# SWITCH.net
KiCad netlist of a schematic drawn in Altium Designer
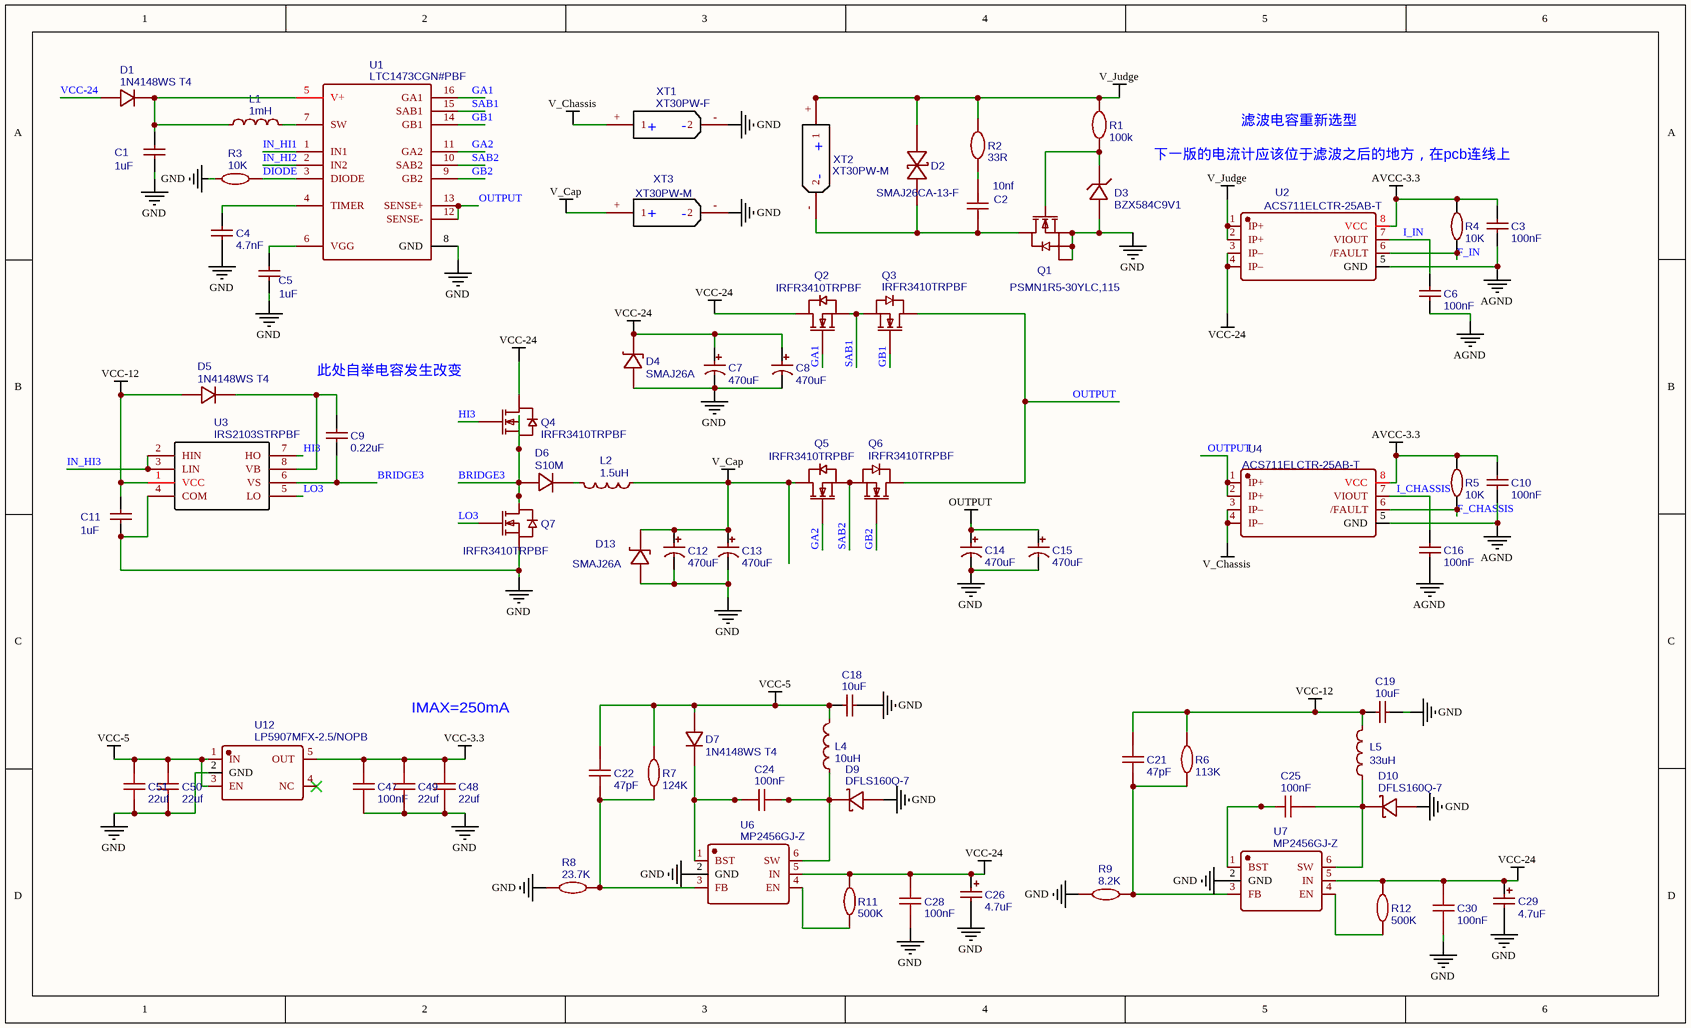
[diagram p0: SWITCH.SchDoc]

(export (version "E")
  (design (tool "Eeschema 10.0.6"))
  (components
    (comp (ref "C1")
      (value "1uF")
      (footprint "0603")
      (fields
        (field (name "BOM_MANUFACTURER PART") "CL10A105KB8NNNC")
        (field (name "BOM_SUPPLIER PART") "C15849")
      )
      (libsource (lib "altium-import") (part "root_3_1uF_"))
    )
    (comp (ref "C2")
      (value "10nf")
      (footprint "C0603")
      (libsource (lib "altium-import") (part "root_0_10nf_"))
    )
    (comp (ref "C3")
      (value "100nF")
      (footprint "L0603")
      (fields
        (field (name "BOM_MANUFACTURER PART") "CL05B104KO5NNNC")
        (field (name "BOM_SUPPLIER PART") "C1525")
      )
      (libsource (lib "") (part "root_1_100nF__1"))
    )
    (comp (ref "C4")
      (value "4.7nF")
      (footprint "C0603")
      (fields
        (field (name "BOM_MANUFACTURER PART") "0805B472K500NT")
        (field (name "BOM_SUPPLIER PART") "C1744")
      )
      (libsource (lib "altium-import") (part "root_1_4.7nF_"))
    )
    (comp (ref "C5")
      (value "1uF")
      (footprint "0603")
      (fields
        (field (name "BOM_MANUFACTURER PART") "CL10A105KB8NNNC")
        (field (name "BOM_SUPPLIER PART") "C15849")
      )
      (libsource (lib "altium-import") (part "root_3_1uF_"))
    )
    (comp (ref "C6")
      (value "100nF")
      (footprint "L0603")
      (fields
        (field (name "BOM_MANUFACTURER PART") "CL05B104KO5NNNC")
        (field (name "BOM_SUPPLIER PART") "C1525")
      )
      (libsource (lib "") (part "root_1_100nF__1"))
    )
    (comp (ref "C7")
      (value "470uF")
      (footprint "CAP-D12.5XF5.0")
      (fields (field (name "BOM_MANUFACTURER PART") "470μF 63V") (field (name "BOM_SUPPLIER PART") "C18823"))
      (libsource (lib "altium-import") (part "root_3_470uF_"))
    )
    (comp (ref "C8")
      (value "470uF")
      (footprint "CAP-D12.5XF5.0")
      (fields (field (name "BOM_MANUFACTURER PART") "470μF 63V") (field (name "BOM_SUPPLIER PART") "C18823"))
      (libsource (lib "altium-import") (part "root_3_470uF_"))
    )
    (comp (ref "C9")
      (value "0.22uF")
      (footprint "C0603")
      (libsource (lib "altium-import") (part "root_1_0.22uF_"))
    )
    (comp (ref "C10")
      (value "100nF")
      (footprint "L0603")
      (fields
        (field (name "BOM_MANUFACTURER PART") "CL05B104KO5NNNC")
        (field (name "BOM_SUPPLIER PART") "C1525")
      )
      (libsource (lib "") (part "root_1_100nF__1"))
    )
    (comp (ref "C11")
      (value "1uF")
      (footprint "0603")
      (fields
        (field (name "BOM_MANUFACTURER PART") "CL10A105KB8NNNC")
        (field (name "BOM_SUPPLIER PART") "C15849")
      )
      (libsource (lib "altium-import") (part "root_3_1uF_"))
    )
    (comp (ref "C12")
      (value "470uF")
      (footprint "CAP-D12.5XF5.0")
      (fields (field (name "BOM_MANUFACTURER PART") "470μF 63V") (field (name "BOM_SUPPLIER PART") "C18823"))
      (libsource (lib "altium-import") (part "root_3_470uF_"))
    )
    (comp (ref "C13")
      (value "470uF")
      (footprint "CAP-D12.5XF5.0")
      (fields (field (name "BOM_MANUFACTURER PART") "470μF 63V") (field (name "BOM_SUPPLIER PART") "C18823"))
      (libsource (lib "altium-import") (part "root_3_470uF_"))
    )
    (comp (ref "C14")
      (value "470uF")
      (footprint "CAP-D12.5XF5.0")
      (fields (field (name "BOM_MANUFACTURER PART") "470μF 63V") (field (name "BOM_SUPPLIER PART") "C18823"))
      (libsource (lib "altium-import") (part "root_3_470uF_"))
    )
    (comp (ref "C15")
      (value "470uF")
      (footprint "CAP-D12.5XF5.0")
      (fields (field (name "BOM_MANUFACTURER PART") "470μF 63V") (field (name "BOM_SUPPLIER PART") "C18823"))
      (libsource (lib "altium-import") (part "root_3_470uF_"))
    )
    (comp (ref "C16")
      (value "100nF")
      (footprint "L0603")
      (fields
        (field (name "BOM_MANUFACTURER PART") "CL05B104KO5NNNC")
        (field (name "BOM_SUPPLIER PART") "C1525")
      )
      (libsource (lib "") (part "root_1_100nF__1"))
    )
    (comp (ref "C18")
      (value "10uF")
      (footprint "0805")
      (fields
        (field (name "BOM_MANUFACTURER PART") "CL21A106KAYNNNE")
        (field (name "BOM_SUPPLIER PART") "C15850")
      )
      (libsource (lib "altium-import") (part "root_0_10uF_"))
    )
    (comp (ref "C19")
      (value "10uF")
      (footprint "0805")
      (fields
        (field (name "BOM_MANUFACTURER PART") "CL21A106KAYNNNE")
        (field (name "BOM_SUPPLIER PART") "C15850")
      )
      (libsource (lib "altium-import") (part "root_0_10uF_"))
    )
    (comp (ref "C21")
      (value "47pF")
      (footprint "0603")
      (fields
        (field (name "BOM_SUPPLIER PART") "C149616")
        (field (name "BOM_MANUFACTURER PART") "AC0603JRNPO9BN470")
        (field (name "CONTRIBUTOR") "LCSC")
      )
      (libsource (lib "altium-import") (part "root_2_47pF_"))
    )
    (comp (ref "C22")
      (value "47pF")
      (footprint "0603")
      (fields
        (field (name "BOM_SUPPLIER PART") "C149616")
        (field (name "BOM_MANUFACTURER PART") "AC0603JRNPO9BN470")
        (field (name "CONTRIBUTOR") "LCSC")
      )
      (libsource (lib "altium-import") (part "root_2_47pF_"))
    )
    (comp (ref "C24")
      (value "100nF")
      (footprint "0603")
      (fields
        (field (name "BOM_MANUFACTURER PART") "CC0603KRX7R9BB104")
        (field (name "BOM_SUPPLIER PART") "C14663")
      )
      (libsource (lib "altium-import") (part "root_0_100nF_"))
    )
    (comp (ref "C25")
      (value "100nF")
      (footprint "0603")
      (fields
        (field (name "BOM_MANUFACTURER PART") "CC0603KRX7R9BB104")
        (field (name "BOM_SUPPLIER PART") "C14663")
      )
      (libsource (lib "altium-import") (part "root_0_100nF_"))
    )
    (comp (ref "C26")
      (value "4.7uF")
      (footprint "CAP-CASE-A_3216")
      (fields
        (field (name "BOM_MANUFACTURER PART") "CA45-A-25V-4.7UF-K")
        (field (name "BOM_SUPPLIER PART") "C129569")
      )
      (libsource (lib "altium-import") (part "root_3_4.7uF_"))
    )
    (comp (ref "C28")
      (value "100nF")
      (footprint "0603")
      (fields
        (field (name "BOM_MANUFACTURER PART") "CC0603KRX7R9BB104")
        (field (name "BOM_SUPPLIER PART") "C14663")
      )
      (libsource (lib "altium-import") (part "root_1_100nF_"))
    )
    (comp (ref "C29")
      (value "4.7uF")
      (footprint "CAP-CASE-A_3216")
      (fields
        (field (name "BOM_MANUFACTURER PART") "CA45-A-25V-4.7UF-K")
        (field (name "BOM_SUPPLIER PART") "C129569")
      )
      (libsource (lib "altium-import") (part "root_3_4.7uF_"))
    )
    (comp (ref "C30")
      (value "100nF")
      (footprint "0603")
      (fields
        (field (name "BOM_MANUFACTURER PART") "CC0603KRX7R9BB104")
        (field (name "BOM_SUPPLIER PART") "C14663")
      )
      (libsource (lib "altium-import") (part "root_1_100nF_"))
    )
    (comp (ref "C47")
      (value "100nF")
      (footprint "C0603")
      (fields
        (field (name "BOM_MANUFACTURER PART") "GRM188R71H104KA93D")
        (field (name "BOM_SUPPLIER PART") "C77055")
      )
      (libsource (lib "altium-import") (part "root_1_100nF_"))
    )
    (comp (ref "C48")
      (value "22uf")
      (footprint "C0805")
      (fields (field (name "BOM_SUPPLIER PART") "C19704") (field (name "CONTRIBUTOR") "LCSC"))
      (libsource (lib "altium-import") (part "root_0_22uf_"))
    )
    (comp (ref "C49")
      (value "22uf")
      (footprint "C0805")
      (fields (field (name "BOM_SUPPLIER PART") "C19704") (field (name "CONTRIBUTOR") "LCSC"))
      (libsource (lib "altium-import") (part "root_0_22uf_"))
    )
    (comp (ref "C50")
      (value "22uf")
      (footprint "C0805")
      (fields (field (name "BOM_SUPPLIER PART") "C19704") (field (name "CONTRIBUTOR") "LCSC"))
      (libsource (lib "altium-import") (part "root_0_22uf_"))
    )
    (comp (ref "C51")
      (value "22uf")
      (footprint "C0805")
      (fields (field (name "BOM_SUPPLIER PART") "C19704") (field (name "CONTRIBUTOR") "LCSC"))
      (libsource (lib "altium-import") (part "root_0_22uf_"))
    )
    (comp (ref "D1")
      (value "1N4148WS T4")
      (footprint "SOD-323_L1.8-W1.3-LS2.5-FD")
      (fields (field (name "BOM_SUPPLIER PART") "C2128"))
      (libsource (lib "altium-import") (part "root_0_1N4148WS T4_"))
    )
    (comp (ref "D2")
      (value "SMAJ26CA-13-F")
      (footprint "SMA_L4.4-W2.6-LS5.0-BI")
      (fields (field (name "BOM_SUPPLIER PART") "C134976") (field (name "CONTRIBUTOR") "LCSC"))
      (libsource (lib "altium-import") (part "root_1_SMAJ26CA-13-F_"))
    )
    (comp (ref "D3")
      (value "BZX584C9V1")
      (footprint "SOD-523F_L1.7-W0.9-LS1.7-RD")
      (libsource (lib "altium-import") (part "root_3_BZX584C9V1_"))
    )
    (comp (ref "D4")
      (value "SMAJ26A")
      (footprint "SMA(DO-214AC)")
      (fields (field (name "BOM_SUPPLIER PART") "C49370"))
      (libsource (lib "altium-import") (part "root_1_SMAJ26A_"))
    )
    (comp (ref "D5")
      (value "1N4148WS T4")
      (footprint "SOD-323_L1.8-W1.3-LS2.5-FD")
      (fields (field (name "BOM_SUPPLIER PART") "C2128"))
      (libsource (lib "altium-import") (part "root_0_1N4148WS T4_"))
    )
    (comp (ref "D6")
      (value "S10M")
      (footprint "SMC(DO-214AB)")
      (fields (field (name "BOM_SUPPLIER PART") "C64933"))
      (libsource (lib "altium-import") (part "root_2_S10M_"))
    )
    (comp (ref "D7")
      (value "1N4148WS T4")
      (footprint "SOD-323_L1.8-W1.3-LS2.5-FD")
      (fields (field (name "BOM_SUPPLIER PART") "C2128"))
      (libsource (lib "altium-import") (part "root_3_1N4148WS T4_"))
    )
    (comp (ref "D9")
      (value "DFLS160Q-7")
      (footprint "POWERDI-123")
      (fields (field (name "BOM_SUPPLIER PART") "C211394") (field (name "CONTRIBUTOR") "LCSC"))
      (libsource (lib "altium-import") (part "root_2_DFLS160Q-7_"))
    )
    (comp (ref "D10")
      (value "DFLS160Q-7")
      (footprint "POWERDI-123")
      (fields (field (name "BOM_SUPPLIER PART") "C211394") (field (name "CONTRIBUTOR") "LCSC"))
      (libsource (lib "altium-import") (part "root_2_DFLS160Q-7_"))
    )
    (comp (ref "D13")
      (value "SMAJ26A")
      (footprint "SMA(DO-214AC)")
      (fields (field (name "BOM_SUPPLIER PART") "C49370"))
      (libsource (lib "altium-import") (part "root_1_SMAJ26A_"))
    )
    (comp (ref "L1")
      (value "1mH")
      (footprint "IND-SMD_L4.0-W4.0")
      (fields
        (field (name "BOM_SUPPLIER PART") "C354594")
        (field (name "BOM_MANUFACTURER PART") "CKCS4030-1mH/M")
        (field (name "CONTRIBUTOR") "LCSC")
      )
      (libsource (lib "altium-import") (part "root_0_1mH_"))
    )
    (comp (ref "L2")
      (value "1.5uH")
      (footprint "SMD-L-13.5X12.8X5.0")
      (fields
        (field (name "BOM_MANUFACTURER PART") "MWSA1205-1R5MT")
        (field (name "BOM_SUPPLIER PART") "C149569")
        (field (name "CONTRIBUTOR") "LCSC")
      )
      (libsource (lib "altium-import") (part "root_2_1.5uH_"))
    )
    (comp (ref "L4")
      (value "10uH")
      (footprint "R0603")
      (fields
        (field (name "BOM_MANUFACTURER PART") "SDFL2012S100KTF")
        (field (name "BOM_SUPPLIER PART") "C1046")
      )
      (libsource (lib "altium-import") (part "root_1_10uH_"))
    )
    (comp (ref "L5")
      (value "33uH")
      (footprint "1008")
      (fields
        (field (name "BOM_MANUFACTURER PART") "NLV25T-330J-PF")
        (field (name "BOM_SUPPLIER PART") "C136257")
      )
      (libsource (lib "altium-import") (part "root_1_33uH_"))
    )
    (comp (ref "Q1")
      (value "PSMN1R5-30YLC,115")
      (footprint "SOT-669_L4.9-W4.0-P1.27-LS6.0-BR")
      (fields (field (name "BOM_SUPPLIER PART") "C427523") (field (name "CONTRIBUTOR") "LCSC"))
      (libsource (lib "altium-import") (part "root_3_PSMN1R5-30YLC,115_"))
    )
    (comp (ref "Q2")
      (value "IRFR3410TRPBF")
      (footprint "TO-252-2")
      (fields (field (name "BOM_SUPPLIER PART") "C3016"))
      (libsource (lib "") (part "root_1_IRFR3410TRPBF__1"))
    )
    (comp (ref "Q3")
      (value "IRFR3410TRPBF")
      (footprint "TO-252-2")
      (fields (field (name "BOM_SUPPLIER PART") "C3016"))
      (libsource (lib "altium-import") (part "root_1_IRFR3410TRPBF_"))
    )
    (comp (ref "Q4")
      (value "IRFR3410TRPBF")
      (footprint "TO-252-2")
      (fields (field (name "BOM_SUPPLIER PART") "C3016"))
      (libsource (lib "altium-import") (part "root_0_IRFR3410TRPBF_"))
    )
    (comp (ref "Q5")
      (value "IRFR3410TRPBF")
      (footprint "TO-252-2")
      (fields (field (name "BOM_SUPPLIER PART") "C3016"))
      (libsource (lib "") (part "root_1_IRFR3410TRPBF__1"))
    )
    (comp (ref "Q6")
      (value "IRFR3410TRPBF")
      (footprint "TO-252-2")
      (fields (field (name "BOM_SUPPLIER PART") "C3016"))
      (libsource (lib "altium-import") (part "root_1_IRFR3410TRPBF_"))
    )
    (comp (ref "Q7")
      (value "IRFR3410TRPBF")
      (footprint "TO-252-2")
      (fields (field (name "BOM_SUPPLIER PART") "C3016"))
      (libsource (lib "altium-import") (part "root_0_IRFR3410TRPBF_"))
    )
    (comp (ref "R1")
      (value "100k")
      (footprint "R0603")
      (libsource (lib "altium-import") (part "root_1_100k_"))
    )
    (comp (ref "R2") (value "33R") (footprint "R0603") (libsource (lib "altium-import") (part "root_1_33R_")))
    (comp (ref "R3")
      (value "10K")
      (footprint "R0603")
      (fields
        (field (name "BOM_SUPPLIER PART") "C191557")
        (field (name "BOM_MANUFACTURER PART") "ERJ-6RBD1002V")
        (field (name "CONTRIBUTOR") "LCSC")
      )
      (libsource (lib "altium-import") (part "root_0_10K_"))
    )
    (comp (ref "R4")
      (value "10K")
      (footprint "R0603")
      (fields
        (field (name "BOM_MANUFACTURER PART") "0402WGF1002TCE")
        (field (name "BOM_SUPPLIER PART") "C25744")
      )
      (libsource (lib "altium-import") (part "root_1_10K_"))
    )
    (comp (ref "R5")
      (value "10K")
      (footprint "R0603")
      (fields
        (field (name "BOM_MANUFACTURER PART") "0402WGF1002TCE")
        (field (name "BOM_SUPPLIER PART") "C25744")
      )
      (libsource (lib "altium-import") (part "root_1_10K_"))
    )
    (comp (ref "R6")
      (value "113K")
      (footprint "R0603")
      (fields
        (field (name "BOM_SUPPLIER PART") "C228262")
        (field (name "BOM_MANUFACTURER PART") "AC0805FR-07113KL")
        (field (name "CONTRIBUTOR") "LCSC")
      )
      (libsource (lib "altium-import") (part "root_1_113K_"))
    )
    (comp (ref "R7")
      (value "124K")
      (footprint "R0603")
      (fields
        (field (name "BOM_SUPPLIER PART") "C228280")
        (field (name "BOM_MANUFACTURER PART") "AC0805FR-07124KL")
        (field (name "CONTRIBUTOR") "LCSC")
      )
      (libsource (lib "altium-import") (part "root_1_124K_"))
    )
    (comp (ref "R8")
      (value "23.7K")
      (footprint "0805")
      (fields
        (field (name "BOM_SUPPLIER PART") "C322370")
        (field (name "BOM_MANUFACTURER PART") "RS-05K2372FT")
        (field (name "CONTRIBUTOR") "LCSC")
      )
      (libsource (lib "altium-import") (part "root_0_23.7K_"))
    )
    (comp (ref "R9")
      (value "8.2K")
      (footprint "R0603")
      (fields
        (field (name "BOM_MANUFACTURER PART") "WR08X822JTL")
        (field (name "BOM_SUPPLIER PART") "C171042")
        (field (name "CONTRIBUTOR") "LCSC")
      )
      (libsource (lib "altium-import") (part "root_0_8.2K_"))
    )
    (comp (ref "R11")
      (value "500K")
      (footprint "0805")
      (fields
        (field (name "BOM_SUPPLIER PART") "C316218")
        (field (name "BOM_MANUFACTURER PART") "AR05BTCW5003")
        (field (name "CONTRIBUTOR") "LCSC")
      )
      (libsource (lib "altium-import") (part "root_1_500K_"))
    )
    (comp (ref "R12")
      (value "500K")
      (footprint "0805")
      (fields
        (field (name "BOM_SUPPLIER PART") "C316218")
        (field (name "BOM_MANUFACTURER PART") "AR05BTCW5003")
        (field (name "CONTRIBUTOR") "LCSC")
      )
      (libsource (lib "altium-import") (part "root_3_500K_"))
    )
    (comp (ref "U1")
      (value "LTC1473CGN#PBF")
      (footprint "TSSOP16")
      (libsource (lib "altium-import") (part "root_0_LTC1473CGN#PBF_"))
    )
    (comp (ref "U2")
      (value "ACS711ELCTR-25AB-T")
      (footprint "SOIC-8_150MIL")
      (fields (field (name "BOM_SUPPLIER PART") "C114268") (field (name "CONTRIBUTOR") "LCSC"))
      (libsource (lib "altium-import") (part "root_0_ACS711ELCTR-25AB-T_"))
    )
    (comp (ref "U3")
      (value "IRS2103STRPBF")
      (footprint "SOIC-8_150MIL")
      (fields (field (name "BOM_SUPPLIER PART") "C2958"))
      (libsource (lib "altium-import") (part "root_0_IRS2103STRPBF_"))
    )
    (comp (ref "U4")
      (value "ACS711ELCTR-25AB-T")
      (footprint "SOIC-8_150MIL")
      (fields (field (name "BOM_SUPPLIER PART") "C114268") (field (name "CONTRIBUTOR") "LCSC"))
      (libsource (lib "altium-import") (part "root_0_ACS711ELCTR-25AB-T_"))
    )
    (comp (ref "U6")
      (value "MP2456GJ-Z")
      (footprint "TSOT-23-6")
      (fields (field (name "BOM_SUPPLIER PART") "C88045"))
      (libsource (lib "altium-import") (part "root_0_MP2456GJ-Z_"))
    )
    (comp (ref "U7")
      (value "MP2456GJ-Z")
      (footprint "TSOT-23-6")
      (fields (field (name "BOM_SUPPLIER PART") "C88045"))
      (libsource (lib "altium-import") (part "root_0_MP2456GJ-Z_"))
    )
    (comp (ref "U12")
      (value "LP5907MFX-2.5/NOPB")
      (footprint "SOT-23-5_L3.0-W1.7-P0.95-LS2.8-BL")
      (fields (field (name "BOM_SUPPLIER PART") "C165132") (field (name "CONTRIBUTOR") "LCSC"))
      (libsource (lib "altium-import") (part "root_0_LP5907MFX-2.5/NOPB_"))
    )
    (comp (ref "XT1")
      (value "XT30PW-F")
      (footprint "XT30_H_F")
      (fields (field (name "BOM_MANUFACTURER PART") "XT60") (field (name "CONTRIBUTOR") "4bucks"))
      (libsource (lib "altium-import") (part "root_0_XT30PW-F_"))
    )
    (comp (ref "XT2")
      (value "XT30PW-M")
      (footprint "XT30PW")
      (fields (field (name "BOM_MANUFACTURER PART") "XT60") (field (name "CONTRIBUTOR") "4bucks"))
      (libsource (lib "altium-import") (part "root_3_XT30PW-M_"))
    )
    (comp (ref "XT3")
      (value "XT30PW-M")
      (footprint "XT30PW")
      (fields (field (name "BOM_MANUFACTURER PART") "XT60") (field (name "CONTRIBUTOR") "4bucks"))
      (libsource (lib "altium-import") (part "root_0_XT30PW-M_"))
    )
  )
  (nets
    (net (code "1") (name "/BRIDGE3") (class "Default")
      (node (ref "C9") (pin "1") (pinfunction "1_1") (pintype "passive"))
      (node (ref "D6") (pin "1") (pinfunction "A_1") (pintype "passive"))
      (node (ref "Q4") (pin "3") (pinfunction "S_3") (pintype "passive"))
      (node (ref "Q7") (pin "4") (pinfunction "D_4") (pintype "passive"))
      (node (ref "U3") (pin "6") (pinfunction "VS_6") (pintype "passive"))
    )
    (net (code "2") (name "/DIODE") (class "Default")
      (node (ref "R3") (pin "2") (pinfunction "2_2") (pintype "passive"))
      (node (ref "U1") (pin "3") (pinfunction "DIODE_3") (pintype "passive"))
    )
    (net (code "3") (name "/F_CHASSIS") (class "Default")
      (node (ref "R5") (pin "1") (pinfunction "1_1") (pintype "passive"))
      (node (ref "U4") (pin "6") (pinfunction "/FAULT_6") (pintype "passive"))
    )
    (net (code "4") (name "/F_IN") (class "Default")
      (node (ref "R4") (pin "1") (pinfunction "1_1") (pintype "passive"))
      (node (ref "U2") (pin "6") (pinfunction "/FAULT_6") (pintype "passive"))
    )
    (net (code "5") (name "/GA1") (class "Default")
      (node (ref "Q2") (pin "1") (pinfunction "G_1") (pintype "passive"))
      (node (ref "U1") (pin "16") (pinfunction "GA1_16") (pintype "passive"))
    )
    (net (code "6") (name "/GA2") (class "Default")
      (node (ref "Q5") (pin "1") (pinfunction "G_1") (pintype "passive"))
      (node (ref "U1") (pin "11") (pinfunction "GA2_11") (pintype "passive"))
    )
    (net (code "7") (name "/GB1") (class "Default")
      (node (ref "Q3") (pin "1") (pinfunction "G_1") (pintype "passive"))
      (node (ref "U1") (pin "14") (pinfunction "GB1_14") (pintype "passive"))
    )
    (net (code "8") (name "/GB2") (class "Default")
      (node (ref "Q6") (pin "1") (pinfunction "G_1") (pintype "passive"))
      (node (ref "U1") (pin "9") (pinfunction "GB2_9") (pintype "passive"))
    )
    (net (code "9") (name "/HI3") (class "Default")
      (node (ref "Q4") (pin "1") (pinfunction "G_1") (pintype "passive"))
      (node (ref "U3") (pin "7") (pinfunction "HO_7") (pintype "passive"))
    )
    (net (code "10") (name "/IN_HI1") (class "Default")
      (node (ref "U1") (pin "1") (pinfunction "IN1_1") (pintype "passive"))
    )
    (net (code "11") (name "/IN_HI2") (class "Default")
      (node (ref "U1") (pin "2") (pinfunction "IN2_2") (pintype "passive"))
    )
    (net (code "12") (name "/IN_HI3") (class "Default")
      (node (ref "U3") (pin "2") (pinfunction "HIN_2") (pintype "passive"))
      (node (ref "U3") (pin "3") (pinfunction "LIN_3") (pintype "passive"))
    )
    (net (code "13") (name "/I_CHASSIS") (class "Default")
      (node (ref "C16") (pin "2") (pinfunction "2_2") (pintype "passive"))
      (node (ref "U4") (pin "7") (pinfunction "VIOUT_7") (pintype "passive"))
    )
    (net (code "14") (name "/I_IN") (class "Default")
      (node (ref "C6") (pin "2") (pinfunction "2_2") (pintype "passive"))
      (node (ref "U2") (pin "7") (pinfunction "VIOUT_7") (pintype "passive"))
    )
    (net (code "15") (name "/LO3") (class "Default")
      (node (ref "Q7") (pin "1") (pinfunction "G_1") (pintype "passive"))
      (node (ref "U3") (pin "5") (pinfunction "LO_5") (pintype "passive"))
    )
    (net (code "16") (name "/SAB1") (class "Default")
      (node (ref "Q2") (pin "3") (pinfunction "S_3") (pintype "passive"))
      (node (ref "Q3") (pin "3") (pinfunction "S_3") (pintype "passive"))
      (node (ref "U1") (pin "15") (pinfunction "SAB1_15") (pintype "passive"))
    )
    (net (code "17") (name "/SAB2") (class "Default")
      (node (ref "Q5") (pin "3") (pinfunction "S_3") (pintype "passive"))
      (node (ref "Q6") (pin "3") (pinfunction "S_3") (pintype "passive"))
      (node (ref "U1") (pin "10") (pinfunction "SAB2_10") (pintype "passive"))
    )
    (net (code "18") (name "AGND") (class "Default")
      (node (ref "C10") (pin "1") (pinfunction "1_1") (pintype "passive"))
      (node (ref "C16") (pin "1") (pinfunction "1_1") (pintype "passive"))
      (node (ref "C3") (pin "1") (pinfunction "1_1") (pintype "passive"))
      (node (ref "C6") (pin "1") (pinfunction "1_1") (pintype "passive"))
      (node (ref "U2") (pin "5") (pinfunction "GND_5") (pintype "passive"))
      (node (ref "U4") (pin "5") (pinfunction "GND_5") (pintype "passive"))
    )
    (net (code "19") (name "AVCC-3.3") (class "Default")
      (node (ref "C10") (pin "2") (pinfunction "2_2") (pintype "passive"))
      (node (ref "C3") (pin "2") (pinfunction "2_2") (pintype "passive"))
      (node (ref "R4") (pin "2") (pinfunction "2_2") (pintype "passive"))
      (node (ref "R5") (pin "2") (pinfunction "2_2") (pintype "passive"))
      (node (ref "U2") (pin "8") (pinfunction "VCC_8") (pintype "passive"))
      (node (ref "U4") (pin "8") (pinfunction "VCC_8") (pintype "passive"))
    )
    (net (code "20") (name "GND") (class "Default")
      (node (ref "C1") (pin "2") (pinfunction "2_2") (pintype "passive"))
      (node (ref "C11") (pin "2") (pinfunction "2_2") (pintype "passive"))
      (node (ref "C12") (pin "2") (pinfunction "2_2") (pintype "passive"))
      (node (ref "C13") (pin "2") (pinfunction "2_2") (pintype "passive"))
      (node (ref "C14") (pin "2") (pinfunction "2_2") (pintype "passive"))
      (node (ref "C15") (pin "2") (pinfunction "2_2") (pintype "passive"))
      (node (ref "C18") (pin "2") (pinfunction "2_2") (pintype "passive"))
      (node (ref "C19") (pin "2") (pinfunction "2_2") (pintype "passive"))
      (node (ref "C26") (pin "2") (pinfunction "2_2") (pintype "passive"))
      (node (ref "C28") (pin "1") (pinfunction "1_1") (pintype "passive"))
      (node (ref "C29") (pin "2") (pinfunction "2_2") (pintype "passive"))
      (node (ref "C30") (pin "1") (pinfunction "1_1") (pintype "passive"))
      (node (ref "C4") (pin "1") (pinfunction "1_1") (pintype "passive"))
      (node (ref "C47") (pin "1") (pinfunction "1_1") (pintype "passive"))
      (node (ref "C48") (pin "1") (pinfunction "1_1") (pintype "passive"))
      (node (ref "C49") (pin "1") (pinfunction "1_1") (pintype "passive"))
      (node (ref "C5") (pin "2") (pinfunction "2_2") (pintype "passive"))
      (node (ref "C50") (pin "1") (pinfunction "1_1") (pintype "passive"))
      (node (ref "C51") (pin "1") (pinfunction "1_1") (pintype "passive"))
      (node (ref "C7") (pin "2") (pinfunction "2_2") (pintype "passive"))
      (node (ref "C8") (pin "2") (pinfunction "2_2") (pintype "passive"))
      (node (ref "D10") (pin "2") (pinfunction "2_2") (pintype "passive"))
      (node (ref "D13") (pin "1") (pinfunction "A_1") (pintype "passive"))
      (node (ref "D3") (pin "2") (pinfunction "A_2") (pintype "passive"))
      (node (ref "D4") (pin "1") (pinfunction "A_1") (pintype "passive"))
      (node (ref "D9") (pin "2") (pinfunction "2_2") (pintype "passive"))
      (node (ref "Q1") (pin "1") (pinfunction "S_1") (pintype "passive"))
      (node (ref "Q1") (pin "2") (pinfunction "S_2") (pintype "passive"))
      (node (ref "Q1") (pin "3") (pinfunction "S_3") (pintype "passive"))
      (node (ref "Q7") (pin "3") (pinfunction "S_3") (pintype "passive"))
      (node (ref "R3") (pin "1") (pinfunction "1_1") (pintype "passive"))
      (node (ref "R8") (pin "1") (pinfunction "1_1") (pintype "passive"))
      (node (ref "R9") (pin "1") (pinfunction "1_1") (pintype "passive"))
      (node (ref "U1") (pin "8") (pinfunction "GND_8") (pintype "passive"))
      (node (ref "U12") (pin "2") (pinfunction "GND_2") (pintype "passive"))
      (node (ref "U3") (pin "4") (pinfunction "COM_4") (pintype "passive"))
      (node (ref "U6") (pin "2") (pinfunction "GND_2") (pintype "passive"))
      (node (ref "U7") (pin "2") (pinfunction "GND_2") (pintype "passive"))
      (node (ref "XT1") (pin "-") (pinfunction "2_-") (pintype "passive"))
      (node (ref "XT3") (pin "-") (pinfunction "2_-") (pintype "passive"))
    )
    (net (code "21") (name "Net-(C2-Pad2)") (class "Default")
      (node (ref "C2") (pin "2") (pinfunction "2_2") (pintype "passive"))
      (node (ref "R2") (pin "1") (pinfunction "1_1") (pintype "passive"))
    )
    (net (code "22") (name "Net-(D1-K)") (class "Default")
      (node (ref "C1") (pin "1") (pinfunction "1_1") (pintype "passive"))
      (node (ref "D1") (pin "2") (pinfunction "K_2") (pintype "passive"))
      (node (ref "L1") (pin "1") (pinfunction "1_1") (pintype "passive"))
      (node (ref "U1") (pin "5") (pinfunction "V+_5") (pintype "passive"))
    )
    (net (code "23") (name "Net-(D3-K)") (class "Default")
      (node (ref "D3") (pin "1") (pinfunction "K_1") (pintype "passive"))
      (node (ref "Q1") (pin "4") (pinfunction "G_4") (pintype "passive"))
      (node (ref "R1") (pin "1") (pinfunction "1_1") (pintype "passive"))
    )
    (net (code "24") (name "Net-(D5-K)") (class "Default")
      (node (ref "C9") (pin "2") (pinfunction "2_2") (pintype "passive"))
      (node (ref "D5") (pin "2") (pinfunction "K_2") (pintype "passive"))
      (node (ref "U3") (pin "8") (pinfunction "VB_8") (pintype "passive"))
    )
    (net (code "25") (name "Net-(D6-K)") (class "Default")
      (node (ref "D6") (pin "2") (pinfunction "K_2") (pintype "passive"))
      (node (ref "L2") (pin "2") (pinfunction "2_2") (pintype "passive"))
    )
    (net (code "26") (name "Net-(D7-K)") (class "Default")
      (node (ref "C24") (pin "1") (pinfunction "1_1") (pintype "passive"))
      (node (ref "D7") (pin "2") (pinfunction "K_2") (pintype "passive"))
      (node (ref "U6") (pin "1") (pinfunction "BST_1") (pintype "passive"))
    )
    (net (code "27") (name "Net-(Q1-D)") (class "Default")
      (node (ref "C2") (pin "1") (pinfunction "1_1") (pintype "passive"))
      (node (ref "D2") (pin "1") (pinfunction "1_1") (pintype "passive"))
      (node (ref "Q1") (pin "5") (pinfunction "D_5") (pintype "passive"))
      (node (ref "XT2") (pin "-") (pinfunction "2_-") (pintype "passive"))
    )
    (net (code "28") (name "Net-(U1-SW)") (class "Default")
      (node (ref "L1") (pin "2") (pinfunction "2_2") (pintype "passive"))
      (node (ref "U1") (pin "7") (pinfunction "SW_7") (pintype "passive"))
    )
    (net (code "29") (name "Net-(U1-TIMER)") (class "Default")
      (node (ref "C4") (pin "2") (pinfunction "2_2") (pintype "passive"))
      (node (ref "U1") (pin "4") (pinfunction "TIMER_4") (pintype "passive"))
    )
    (net (code "30") (name "Net-(U1-VGG)") (class "Default")
      (node (ref "C5") (pin "1") (pinfunction "1_1") (pintype "passive"))
      (node (ref "U1") (pin "6") (pinfunction "VGG_6") (pintype "passive"))
    )
    (net (code "31") (name "Net-(U6-EN)") (class "Default")
      (node (ref "R11") (pin "1") (pinfunction "1_1") (pintype "passive"))
      (node (ref "U6") (pin "4") (pinfunction "EN_4") (pintype "passive"))
    )
    (net (code "32") (name "Net-(U6-FB)") (class "Default")
      (node (ref "C22") (pin "2") (pinfunction "2_2") (pintype "passive"))
      (node (ref "R7") (pin "1") (pinfunction "1_1") (pintype "passive"))
      (node (ref "R8") (pin "2") (pinfunction "2_2") (pintype "passive"))
      (node (ref "U6") (pin "3") (pinfunction "FB_3") (pintype "passive"))
    )
    (net (code "33") (name "Net-(U6-SW)") (class "Default")
      (node (ref "C24") (pin "2") (pinfunction "2_2") (pintype "passive"))
      (node (ref "D9") (pin "1") (pinfunction "1_1") (pintype "passive"))
      (node (ref "L4") (pin "1") (pinfunction "1_1") (pintype "passive"))
      (node (ref "U6") (pin "6") (pinfunction "SW_6") (pintype "passive"))
    )
    (net (code "34") (name "Net-(U7-BST)") (class "Default")
      (node (ref "C25") (pin "1") (pinfunction "1_1") (pintype "passive"))
      (node (ref "U7") (pin "1") (pinfunction "BST_1") (pintype "passive"))
    )
    (net (code "35") (name "Net-(U7-EN)") (class "Default")
      (node (ref "R12") (pin "2") (pinfunction "2_2") (pintype "passive"))
      (node (ref "U7") (pin "4") (pinfunction "EN_4") (pintype "passive"))
    )
    (net (code "36") (name "Net-(U7-FB)") (class "Default")
      (node (ref "C21") (pin "2") (pinfunction "2_2") (pintype "passive"))
      (node (ref "R6") (pin "1") (pinfunction "1_1") (pintype "passive"))
      (node (ref "R9") (pin "2") (pinfunction "2_2") (pintype "passive"))
      (node (ref "U7") (pin "3") (pinfunction "FB_3") (pintype "passive"))
    )
    (net (code "37") (name "Net-(U7-SW)") (class "Default")
      (node (ref "C25") (pin "2") (pinfunction "2_2") (pintype "passive"))
      (node (ref "D10") (pin "1") (pinfunction "1_1") (pintype "passive"))
      (node (ref "L5") (pin "1") (pinfunction "1_1") (pintype "passive"))
      (node (ref "U7") (pin "6") (pinfunction "SW_6") (pintype "passive"))
    )
    (net (code "38") (name "OUTPUT") (class "Default")
      (node (ref "C14") (pin "1") (pinfunction "1_1") (pintype "passive"))
      (node (ref "C15") (pin "1") (pinfunction "1_1") (pintype "passive"))
      (node (ref "Q3") (pin "4") (pinfunction "D_4") (pintype "passive"))
      (node (ref "Q6") (pin "4") (pinfunction "D_4") (pintype "passive"))
      (node (ref "U1") (pin "12") (pinfunction "SENSE-_12") (pintype "passive"))
      (node (ref "U1") (pin "13") (pinfunction "SENSE+_13") (pintype "passive"))
      (node (ref "U4") (pin "1") (pinfunction "IP+_1") (pintype "passive"))
      (node (ref "U4") (pin "2") (pinfunction "IP+_2") (pintype "passive"))
    )
    (net (code "39") (name "VCC-3.3") (class "Default")
      (node (ref "C47") (pin "2") (pinfunction "2_2") (pintype "passive"))
      (node (ref "C48") (pin "2") (pinfunction "2_2") (pintype "passive"))
      (node (ref "C49") (pin "2") (pinfunction "2_2") (pintype "passive"))
      (node (ref "U12") (pin "5") (pinfunction "OUT_5") (pintype "passive"))
    )
    (net (code "40") (name "VCC-5") (class "Default")
      (node (ref "C18") (pin "1") (pinfunction "1_1") (pintype "passive"))
      (node (ref "C22") (pin "1") (pinfunction "1_1") (pintype "passive"))
      (node (ref "C50") (pin "2") (pinfunction "2_2") (pintype "passive"))
      (node (ref "C51") (pin "2") (pinfunction "2_2") (pintype "passive"))
      (node (ref "D7") (pin "1") (pinfunction "A_1") (pintype "passive"))
      (node (ref "L4") (pin "2") (pinfunction "2_2") (pintype "passive"))
      (node (ref "R7") (pin "2") (pinfunction "2_2") (pintype "passive"))
      (node (ref "U12") (pin "1") (pinfunction "IN_1") (pintype "passive"))
      (node (ref "U12") (pin "3") (pinfunction "EN_3") (pintype "passive"))
    )
    (net (code "41") (name "VCC-12") (class "Default")
      (node (ref "C11") (pin "1") (pinfunction "1_1") (pintype "passive"))
      (node (ref "C19") (pin "1") (pinfunction "1_1") (pintype "passive"))
      (node (ref "C21") (pin "1") (pinfunction "1_1") (pintype "passive"))
      (node (ref "D5") (pin "1") (pinfunction "A_1") (pintype "passive"))
      (node (ref "L5") (pin "2") (pinfunction "2_2") (pintype "passive"))
      (node (ref "R6") (pin "2") (pinfunction "2_2") (pintype "passive"))
      (node (ref "U3") (pin "1") (pinfunction "VCC_1") (pintype "passive"))
    )
    (net (code "42") (name "VCC-24") (class "Default")
      (node (ref "C26") (pin "1") (pinfunction "1_1") (pintype "passive"))
      (node (ref "C28") (pin "2") (pinfunction "2_2") (pintype "passive"))
      (node (ref "C29") (pin "1") (pinfunction "1_1") (pintype "passive"))
      (node (ref "C30") (pin "2") (pinfunction "2_2") (pintype "passive"))
      (node (ref "C7") (pin "1") (pinfunction "1_1") (pintype "passive"))
      (node (ref "C8") (pin "1") (pinfunction "1_1") (pintype "passive"))
      (node (ref "D1") (pin "1") (pinfunction "A_1") (pintype "passive"))
      (node (ref "D4") (pin "2") (pinfunction "K_2") (pintype "passive"))
      (node (ref "Q2") (pin "4") (pinfunction "D_4") (pintype "passive"))
      (node (ref "Q4") (pin "4") (pinfunction "D_4") (pintype "passive"))
      (node (ref "R11") (pin "2") (pinfunction "2_2") (pintype "passive"))
      (node (ref "R12") (pin "1") (pinfunction "1_1") (pintype "passive"))
      (node (ref "U2") (pin "3") (pinfunction "IP–_3") (pintype "passive"))
      (node (ref "U2") (pin "4") (pinfunction "IP–_4") (pintype "passive"))
      (node (ref "U6") (pin "5") (pinfunction "IN_5") (pintype "passive"))
      (node (ref "U7") (pin "5") (pinfunction "IN_5") (pintype "passive"))
    )
    (net (code "43") (name "V_Cap") (class "Default")
      (node (ref "C12") (pin "1") (pinfunction "1_1") (pintype "passive"))
      (node (ref "C13") (pin "1") (pinfunction "1_1") (pintype "passive"))
      (node (ref "D13") (pin "2") (pinfunction "K_2") (pintype "passive"))
      (node (ref "L2") (pin "1") (pinfunction "1_1") (pintype "passive"))
      (node (ref "Q5") (pin "4") (pinfunction "D_4") (pintype "passive"))
      (node (ref "XT3") (pin "+") (pinfunction "1_+") (pintype "passive"))
    )
    (net (code "44") (name "V_Chassis") (class "Default")
      (node (ref "U4") (pin "3") (pinfunction "IP–_3") (pintype "passive"))
      (node (ref "U4") (pin "4") (pinfunction "IP–_4") (pintype "passive"))
      (node (ref "XT1") (pin "+") (pinfunction "1_+") (pintype "passive"))
    )
    (net (code "45") (name "V_Judge") (class "Default")
      (node (ref "D2") (pin "2") (pinfunction "2_2") (pintype "passive"))
      (node (ref "R1") (pin "2") (pinfunction "2_2") (pintype "passive"))
      (node (ref "R2") (pin "2") (pinfunction "2_2") (pintype "passive"))
      (node (ref "U2") (pin "1") (pinfunction "IP+_1") (pintype "passive"))
      (node (ref "U2") (pin "2") (pinfunction "IP+_2") (pintype "passive"))
      (node (ref "XT2") (pin "+") (pinfunction "1_+") (pintype "passive"))
    )
    (net (code "46") (name "unconnected-(U12-NC-Pad4)") (class "Default")
      (node (ref "U12") (pin "4") (pinfunction "NC_4") (pintype "passive+no_connect"))
    )
  )
)
